# Peripheral.net
KiCad netlist of a schematic drawn in Altium Designer
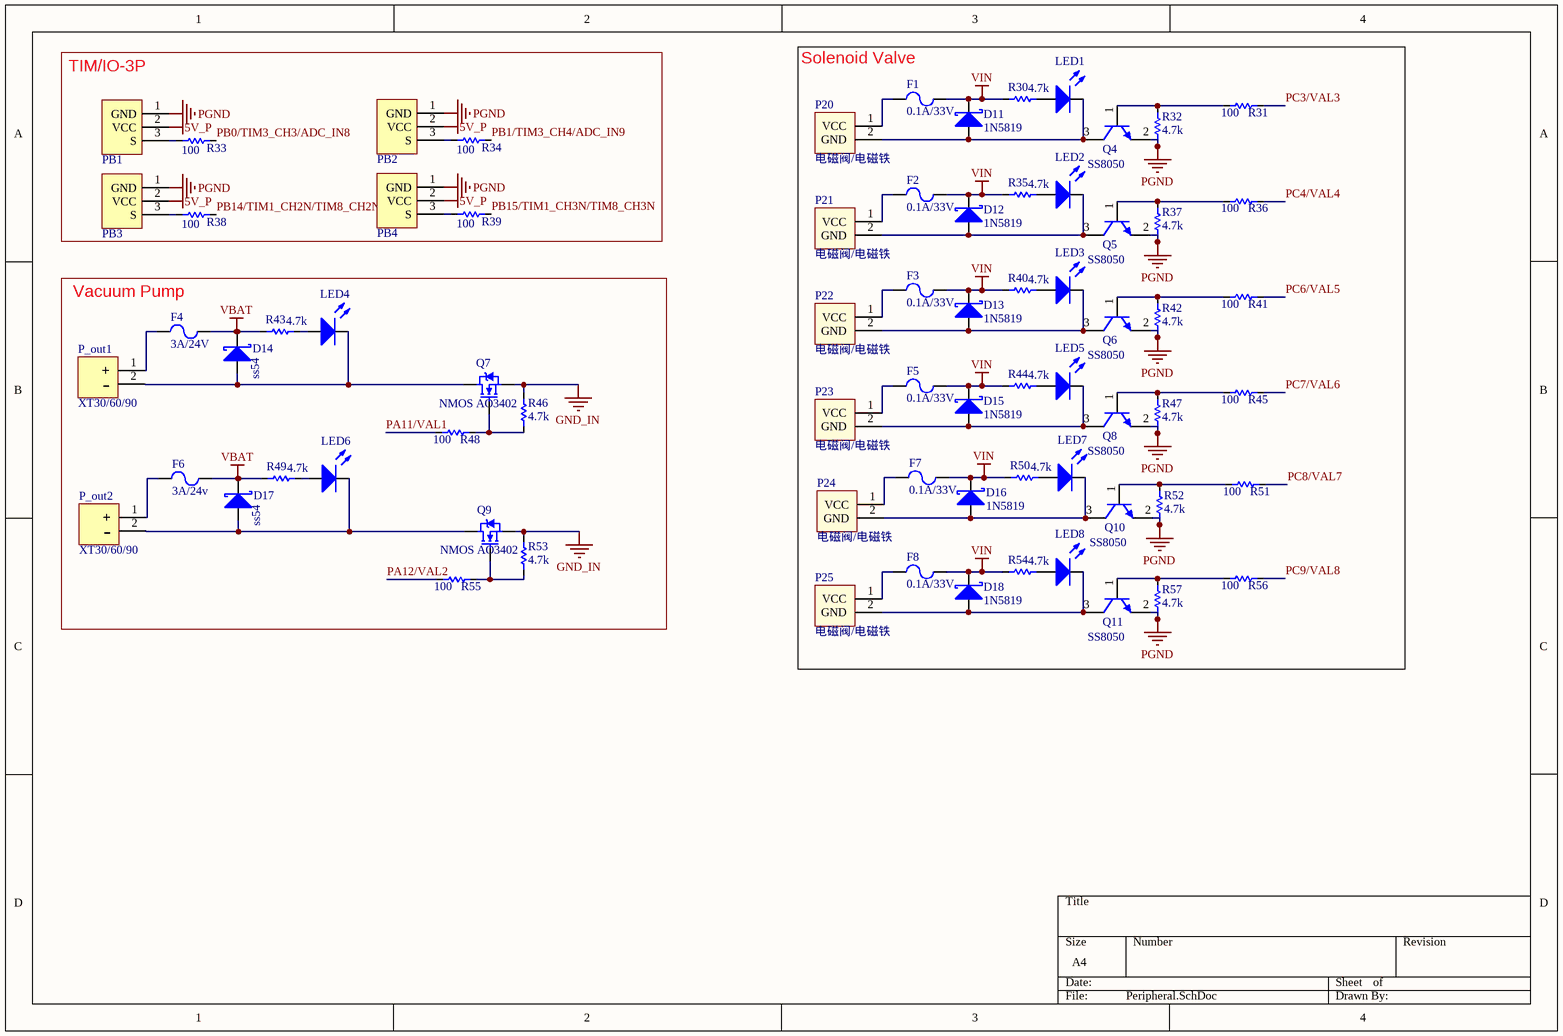
[diagram p0: Peripheral.SchDoc]

(export (version "E")
  (design (tool "Eeschema 10.0.6"))
  (components
    (comp (ref "D11")
      (value "1N5819")
      (footprint "SOD-323-")
      (description "Schottky Diode")
      (fields (field (name "PUBLISHER") "Altium Limited"))
      (libsource (lib "MyComponents_v2.5") (part "D Schottky"))
    )
    (comp (ref "D12")
      (value "1N5819")
      (footprint "SOD-323-")
      (description "Schottky Diode")
      (fields (field (name "PUBLISHER") "Altium Limited"))
      (libsource (lib "MyComponents_v2.5") (part "D Schottky"))
    )
    (comp (ref "D13")
      (value "1N5819")
      (footprint "SOD-323-")
      (description "Schottky Diode")
      (fields (field (name "PUBLISHER") "Altium Limited"))
      (libsource (lib "MyComponents_v2.5") (part "D Schottky"))
    )
    (comp (ref "D14")
      (value "ss54")
      (footprint "SMAF/DO-214AC")
      (description "Schottky Diode")
      (fields (field (name "PUBLISHER") "Altium Limited"))
      (libsource (lib "MyComponents_v2.5") (part "D Schottky_SOD323"))
    )
    (comp (ref "D15")
      (value "1N5819")
      (footprint "SOD-323-")
      (description "Schottky Diode")
      (fields (field (name "PUBLISHER") "Altium Limited"))
      (libsource (lib "MyComponents_v2.5") (part "D Schottky"))
    )
    (comp (ref "D16")
      (value "1N5819")
      (footprint "SOD-323-")
      (description "Schottky Diode")
      (fields (field (name "PUBLISHER") "Altium Limited"))
      (libsource (lib "MyComponents_v2.5") (part "D Schottky"))
    )
    (comp (ref "D17")
      (value "ss54")
      (footprint "SMAF/DO-214AC")
      (description "Schottky Diode")
      (fields (field (name "PUBLISHER") "Altium Limited"))
      (libsource (lib "MyComponents_v2.5") (part "D Schottky_SOD323"))
    )
    (comp (ref "D18")
      (value "1N5819")
      (footprint "SOD-323-")
      (description "Schottky Diode")
      (fields (field (name "PUBLISHER") "Altium Limited"))
      (libsource (lib "MyComponents_v2.5") (part "D Schottky"))
    )
    (comp (ref "F1")
      (value "0.1A/33V")
      (footprint "0603C")
      (description "0603自恢复保险丝")
      (libsource (lib "MyComponents_v2.5") (part "Finance"))
    )
    (comp (ref "F2")
      (value "0.1A/33V")
      (footprint "0603C")
      (description "0603自恢复保险丝")
      (libsource (lib "MyComponents_v2.5") (part "Finance"))
    )
    (comp (ref "F3")
      (value "0.1A/33V")
      (footprint "0603C")
      (description "0603自恢复保险丝")
      (libsource (lib "MyComponents_v2.5") (part "Finance"))
    )
    (comp (ref "F4")
      (value "3A/24V")
      (footprint "0603C")
      (description "0603自恢复保险丝")
      (libsource (lib "MyComponents_v2.5") (part "Finance"))
    )
    (comp (ref "F5")
      (value "0.1A/33V")
      (footprint "0603C")
      (description "0603自恢复保险丝")
      (libsource (lib "MyComponents_v2.5") (part "Finance"))
    )
    (comp (ref "F6")
      (value "3A/24v")
      (footprint "0603C")
      (description "0603自恢复保险丝")
      (libsource (lib "MyComponents_v2.5") (part "Finance"))
    )
    (comp (ref "F7")
      (value "0.1A/33V")
      (footprint "0603C")
      (description "0603自恢复保险丝")
      (libsource (lib "MyComponents_v2.5") (part "Finance"))
    )
    (comp (ref "F8")
      (value "0.1A/33V")
      (footprint "0603C")
      (description "0603自恢复保险丝")
      (libsource (lib "MyComponents_v2.5") (part "Finance"))
    )
    (comp (ref "LED1")
      (value "LED_RED")
      (footprint "0603LED_B")
      (description "Typical RED, GREEN, YELLOW, AMBER GaAs LED")
      (fields (field (name "PUBLISHER") "Altium Limited"))
      (libsource (lib "MyComponents_v2.5") (part "LED"))
    )
    (comp (ref "LED2")
      (value "LED_RED")
      (footprint "0603LED_B")
      (description "Typical RED, GREEN, YELLOW, AMBER GaAs LED")
      (fields (field (name "PUBLISHER") "Altium Limited"))
      (libsource (lib "MyComponents_v2.5") (part "LED"))
    )
    (comp (ref "LED3")
      (value "LED_RED")
      (footprint "0603LED_B")
      (description "Typical RED, GREEN, YELLOW, AMBER GaAs LED")
      (fields (field (name "PUBLISHER") "Altium Limited"))
      (libsource (lib "MyComponents_v2.5") (part "LED"))
    )
    (comp (ref "LED4")
      (value "LED_RED")
      (footprint "0603LED_B")
      (description "Typical RED, GREEN, YELLOW, AMBER GaAs LED")
      (fields (field (name "PUBLISHER") "Altium Limited"))
      (libsource (lib "MyComponents_v2.5") (part "LED"))
    )
    (comp (ref "LED5")
      (value "LED_RED")
      (footprint "0603LED_B")
      (description "Typical RED, GREEN, YELLOW, AMBER GaAs LED")
      (fields (field (name "PUBLISHER") "Altium Limited"))
      (libsource (lib "MyComponents_v2.5") (part "LED"))
    )
    (comp (ref "LED6")
      (value "LED_RED")
      (footprint "0603LED_B")
      (description "Typical RED, GREEN, YELLOW, AMBER GaAs LED")
      (fields (field (name "PUBLISHER") "Altium Limited"))
      (libsource (lib "MyComponents_v2.5") (part "LED"))
    )
    (comp (ref "LED7")
      (value "LED_RED")
      (footprint "0603LED_B")
      (description "Typical RED, GREEN, YELLOW, AMBER GaAs LED")
      (fields (field (name "PUBLISHER") "Altium Limited"))
      (libsource (lib "MyComponents_v2.5") (part "LED"))
    )
    (comp (ref "LED8")
      (value "LED_RED")
      (footprint "0603LED_B")
      (description "Typical RED, GREEN, YELLOW, AMBER GaAs LED")
      (fields (field (name "PUBLISHER") "Altium Limited"))
      (libsource (lib "MyComponents_v2.5") (part "LED"))
    )
    (comp (ref "P20")
      (value "电磁阀/电磁铁")
      (footprint "HY2.00MM 2X1_立式")
      (libsource (lib "MyComponents_v2.5") (part "电磁阀/电磁铁"))
    )
    (comp (ref "P21")
      (value "电磁阀/电磁铁")
      (footprint "HY2.00MM 2X1_立式")
      (libsource (lib "MyComponents_v2.5") (part "电磁阀/电磁铁"))
    )
    (comp (ref "P22")
      (value "电磁阀/电磁铁")
      (footprint "HY2.00MM 2X1_立式")
      (libsource (lib "MyComponents_v2.5") (part "电磁阀/电磁铁"))
    )
    (comp (ref "P23")
      (value "电磁阀/电磁铁")
      (footprint "HY2.00MM 2X1_立式")
      (libsource (lib "MyComponents_v2.5") (part "电磁阀/电磁铁"))
    )
    (comp (ref "P24")
      (value "电磁阀/电磁铁")
      (footprint "HY2.00MM 2X1_立式")
      (libsource (lib "MyComponents_v2.5") (part "电磁阀/电磁铁"))
    )
    (comp (ref "P25")
      (value "电磁阀/电磁铁")
      (footprint "HY2.00MM 2X1_立式")
      (libsource (lib "MyComponents_v2.5") (part "电磁阀/电磁铁"))
    )
    (comp (ref "PB1")
      (value "3Pin_IO")
      (footprint "HY2.00MM 3x1立式")
      (description "3pin input/output. V+S+G")
      (libsource (lib "MyComponents_v2.5") (part "3Pin_IO"))
    )
    (comp (ref "PB2")
      (value "3Pin_IO")
      (footprint "HY2.00MM 3x1立式")
      (description "3pin input/output. V+S+G")
      (libsource (lib "MyComponents_v2.5") (part "3Pin_IO"))
    )
    (comp (ref "PB3")
      (value "3Pin_IO")
      (footprint "HY2.00MM 3x1立式")
      (description "3pin input/output. V+S+G")
      (libsource (lib "MyComponents_v2.5") (part "3Pin_IO"))
    )
    (comp (ref "PB4")
      (value "3Pin_IO")
      (footprint "HY2.00MM 3x1立式")
      (description "3pin input/output. V+S+G")
      (libsource (lib "MyComponents_v2.5") (part "3Pin_IO"))
    )
    (comp (ref "P_out1")
      (value "XT30/60/90")
      (footprint "XT30UPB-FEMALE")
      (libsource (lib "MyComponents_v2.5") (part "XT30/60/90"))
    )
    (comp (ref "P_out2")
      (value "XT30/60/90")
      (footprint "XT30UPB-FEMALE")
      (libsource (lib "MyComponents_v2.5") (part "XT30/60/90"))
    )
    (comp (ref "Q4")
      (value "SS8050")
      (footprint "SOT-23-3")
      (description "NPN Bipolar Transistor")
      (fields (field (name "PUBLISHER") "Altium Limited"))
      (libsource (lib "MyComponents_v2.5") (part "NPN"))
    )
    (comp (ref "Q5")
      (value "SS8050")
      (footprint "SOT-23-3")
      (description "NPN Bipolar Transistor")
      (fields (field (name "PUBLISHER") "Altium Limited"))
      (libsource (lib "MyComponents_v2.5") (part "NPN"))
    )
    (comp (ref "Q6")
      (value "SS8050")
      (footprint "SOT-23-3")
      (description "NPN Bipolar Transistor")
      (fields (field (name "PUBLISHER") "Altium Limited"))
      (libsource (lib "MyComponents_v2.5") (part "NPN"))
    )
    (comp (ref "Q7")
      (value "NMOS AO3402")
      (footprint "SOT-23-3")
      (description "N-Channel Power MOSFET")
      (fields (field (name "PUBLISHER") "Altium Limited"))
      (libsource (lib "MyComponents_v2.5") (part "NMOS(SOT23)"))
    )
    (comp (ref "Q8")
      (value "SS8050")
      (footprint "SOT-23-3")
      (description "NPN Bipolar Transistor")
      (fields (field (name "PUBLISHER") "Altium Limited"))
      (libsource (lib "MyComponents_v2.5") (part "NPN"))
    )
    (comp (ref "Q9")
      (value "NMOS AO3402")
      (footprint "SOT-23-3")
      (description "N-Channel Power MOSFET")
      (fields (field (name "PUBLISHER") "Altium Limited"))
      (libsource (lib "MyComponents_v2.5") (part "NMOS(SOT23)"))
    )
    (comp (ref "Q10")
      (value "SS8050")
      (footprint "SOT-23-3")
      (description "NPN Bipolar Transistor")
      (fields (field (name "PUBLISHER") "Altium Limited"))
      (libsource (lib "MyComponents_v2.5") (part "NPN"))
    )
    (comp (ref "Q11")
      (value "SS8050")
      (footprint "SOT-23-3")
      (description "NPN Bipolar Transistor")
      (fields (field (name "PUBLISHER") "Altium Limited"))
      (libsource (lib "MyComponents_v2.5") (part "NPN"))
    )
    (comp (ref "R30")
      (value "4.7k")
      (footprint "0603R")
      (description "Resistor")
      (fields (field (name "PUBLISHER") "Altium Limited"))
      (libsource (lib "MyComponents_v2.5") (part "Res1"))
    )
    (comp (ref "R31")
      (value "100")
      (footprint "0603R")
      (description "Resistor")
      (fields (field (name "PUBLISHER") "Altium Limited"))
      (libsource (lib "MyComponents_v2.5") (part "Res1"))
    )
    (comp (ref "R32")
      (value "4.7k")
      (footprint "0603R")
      (description "Resistor")
      (fields (field (name "PUBLISHER") "Altium Limited"))
      (libsource (lib "MyComponents_v2.4") (part "Res1"))
    )
    (comp (ref "R33")
      (value "100")
      (footprint "0603R")
      (description "Resistor")
      (fields (field (name "PUBLISHER") "Altium Limited"))
      (libsource (lib "MyComponents_v2.5") (part "Res1"))
    )
    (comp (ref "R34")
      (value "100")
      (footprint "0603R")
      (description "Resistor")
      (fields (field (name "PUBLISHER") "Altium Limited"))
      (libsource (lib "MyComponents_v2.5") (part "Res1"))
    )
    (comp (ref "R35")
      (value "4.7k")
      (footprint "0603R")
      (description "Resistor")
      (fields (field (name "PUBLISHER") "Altium Limited"))
      (libsource (lib "MyComponents_v2.5") (part "Res1"))
    )
    (comp (ref "R36")
      (value "100")
      (footprint "0603R")
      (description "Resistor")
      (fields (field (name "PUBLISHER") "Altium Limited"))
      (libsource (lib "MyComponents_v2.5") (part "Res1"))
    )
    (comp (ref "R37")
      (value "4.7k")
      (footprint "0603R")
      (description "Resistor")
      (fields (field (name "PUBLISHER") "Altium Limited"))
      (libsource (lib "MyComponents_v2.4") (part "Res1"))
    )
    (comp (ref "R38")
      (value "100")
      (footprint "0603R")
      (description "Resistor")
      (fields (field (name "PUBLISHER") "Altium Limited"))
      (libsource (lib "MyComponents_v2.5") (part "Res1"))
    )
    (comp (ref "R39")
      (value "100")
      (footprint "0603R")
      (description "Resistor")
      (fields (field (name "PUBLISHER") "Altium Limited"))
      (libsource (lib "MyComponents_v2.5") (part "Res1"))
    )
    (comp (ref "R40")
      (value "4.7k")
      (footprint "0603R")
      (description "Resistor")
      (fields (field (name "PUBLISHER") "Altium Limited"))
      (libsource (lib "MyComponents_v2.5") (part "Res1"))
    )
    (comp (ref "R41")
      (value "100")
      (footprint "0603R")
      (description "Resistor")
      (fields (field (name "PUBLISHER") "Altium Limited"))
      (libsource (lib "MyComponents_v2.5") (part "Res1"))
    )
    (comp (ref "R42")
      (value "4.7k")
      (footprint "0603R")
      (description "Resistor")
      (fields (field (name "PUBLISHER") "Altium Limited"))
      (libsource (lib "MyComponents_v2.4") (part "Res1"))
    )
    (comp (ref "R43")
      (value "4.7k")
      (footprint "0603R")
      (description "Resistor")
      (fields (field (name "PUBLISHER") "Altium Limited"))
      (libsource (lib "MyComponents_v2.5") (part "Res1"))
    )
    (comp (ref "R44")
      (value "4.7k")
      (footprint "0603R")
      (description "Resistor")
      (fields (field (name "PUBLISHER") "Altium Limited"))
      (libsource (lib "MyComponents_v2.5") (part "Res1"))
    )
    (comp (ref "R45")
      (value "100")
      (footprint "0603R")
      (description "Resistor")
      (fields (field (name "PUBLISHER") "Altium Limited"))
      (libsource (lib "MyComponents_v2.5") (part "Res1"))
    )
    (comp (ref "R46")
      (value "4.7k")
      (footprint "0603R")
      (description "Resistor")
      (fields (field (name "PUBLISHER") "Altium Limited"))
      (libsource (lib "MyComponents_v2.4") (part "Res1"))
    )
    (comp (ref "R47")
      (value "4.7k")
      (footprint "0603R")
      (description "Resistor")
      (fields (field (name "PUBLISHER") "Altium Limited"))
      (libsource (lib "MyComponents_v2.4") (part "Res1"))
    )
    (comp (ref "R48")
      (value "100")
      (footprint "0603R")
      (description "Resistor")
      (fields (field (name "PUBLISHER") "Altium Limited"))
      (libsource (lib "MyComponents_v2.5") (part "Res1"))
    )
    (comp (ref "R49")
      (value "4.7k")
      (footprint "0603R")
      (description "Resistor")
      (fields (field (name "PUBLISHER") "Altium Limited"))
      (libsource (lib "MyComponents_v2.5") (part "Res1"))
    )
    (comp (ref "R50")
      (value "4.7k")
      (footprint "0603R")
      (description "Resistor")
      (fields (field (name "PUBLISHER") "Altium Limited"))
      (libsource (lib "MyComponents_v2.5") (part "Res1"))
    )
    (comp (ref "R51")
      (value "100")
      (footprint "0603R")
      (description "Resistor")
      (fields (field (name "PUBLISHER") "Altium Limited"))
      (libsource (lib "MyComponents_v2.5") (part "Res1"))
    )
    (comp (ref "R52")
      (value "4.7k")
      (footprint "0603R")
      (description "Resistor")
      (fields (field (name "PUBLISHER") "Altium Limited"))
      (libsource (lib "MyComponents_v2.4") (part "Res1"))
    )
    (comp (ref "R53")
      (value "4.7k")
      (footprint "0603R")
      (description "Resistor")
      (fields (field (name "PUBLISHER") "Altium Limited"))
      (libsource (lib "MyComponents_v2.4") (part "Res1"))
    )
    (comp (ref "R54")
      (value "4.7k")
      (footprint "0603R")
      (description "Resistor")
      (fields (field (name "PUBLISHER") "Altium Limited"))
      (libsource (lib "MyComponents_v2.5") (part "Res1"))
    )
    (comp (ref "R55")
      (value "100")
      (footprint "0603R")
      (description "Resistor")
      (fields (field (name "PUBLISHER") "Altium Limited"))
      (libsource (lib "MyComponents_v2.5") (part "Res1"))
    )
    (comp (ref "R56")
      (value "100")
      (footprint "0603R")
      (description "Resistor")
      (fields (field (name "PUBLISHER") "Altium Limited"))
      (libsource (lib "MyComponents_v2.5") (part "Res1"))
    )
    (comp (ref "R57")
      (value "4.7k")
      (footprint "0603R")
      (description "Resistor")
      (fields (field (name "PUBLISHER") "Altium Limited"))
      (libsource (lib "MyComponents_v2.4") (part "Res1"))
    )
  )
  (nets
    (net (code "1") (name "/PA11{slash}VAL1") (class "Default")
      (node (ref "R48") (pin "1") (pinfunction "1_1") (pintype "passive"))
    )
    (net (code "2") (name "/PA12{slash}VAL2") (class "Default")
      (node (ref "R55") (pin "1") (pinfunction "1_1") (pintype "passive"))
    )
    (net (code "3") (name "/PB0{slash}TIM3_CH3{slash}ADC_IN8") (class "Default")
      (node (ref "R33") (pin "2") (pinfunction "2_2") (pintype "passive"))
    )
    (net (code "4") (name "/PB1{slash}TIM3_CH4{slash}ADC_IN9") (class "Default")
      (node (ref "R34") (pin "2") (pinfunction "2_2") (pintype "passive"))
    )
    (net (code "5") (name "/PB14{slash}TIM1_CH2N{slash}TIM8_CH2N") (class "Default")
      (node (ref "R38") (pin "2") (pinfunction "2_2") (pintype "passive"))
    )
    (net (code "6") (name "/PB15{slash}TIM1_CH3N{slash}TIM8_CH3N") (class "Default")
      (node (ref "R39") (pin "2") (pinfunction "2_2") (pintype "passive"))
    )
    (net (code "7") (name "/PC3{slash}VAL3") (class "Default")
      (node (ref "R31") (pin "2") (pinfunction "2_2") (pintype "passive"))
    )
    (net (code "8") (name "/PC4{slash}VAL4") (class "Default")
      (node (ref "R36") (pin "2") (pinfunction "2_2") (pintype "passive"))
    )
    (net (code "9") (name "/PC6{slash}VAL5") (class "Default")
      (node (ref "R41") (pin "2") (pinfunction "2_2") (pintype "passive"))
    )
    (net (code "10") (name "/PC7{slash}VAL6") (class "Default")
      (node (ref "R45") (pin "2") (pinfunction "2_2") (pintype "passive"))
    )
    (net (code "11") (name "/PC8{slash}VAL7") (class "Default")
      (node (ref "R51") (pin "2") (pinfunction "2_2") (pintype "passive"))
    )
    (net (code "12") (name "/PC9{slash}VAL8") (class "Default")
      (node (ref "R56") (pin "2") (pinfunction "2_2") (pintype "passive"))
    )
    (net (code "13") (name "5V_P") (class "Default")
      (node (ref "PB1") (pin "2") (pinfunction "VCC_2") (pintype "passive"))
      (node (ref "PB2") (pin "2") (pinfunction "VCC_2") (pintype "passive"))
      (node (ref "PB3") (pin "2") (pinfunction "VCC_2") (pintype "passive"))
      (node (ref "PB4") (pin "2") (pinfunction "VCC_2") (pintype "passive"))
    )
    (net (code "14") (name "GND_IN") (class "Default")
      (node (ref "Q7") (pin "2") (pinfunction "S_2") (pintype "passive"))
      (node (ref "Q9") (pin "2") (pinfunction "S_2") (pintype "passive"))
      (node (ref "R46") (pin "2") (pinfunction "2_2") (pintype "passive"))
      (node (ref "R53") (pin "2") (pinfunction "2_2") (pintype "passive"))
    )
    (net (code "15") (name "Net-(LED1-Pad1)") (class "Default")
      (node (ref "LED1") (pin "1") (pinfunction "1_1") (pintype "passive"))
      (node (ref "R30") (pin "2") (pinfunction "2_2") (pintype "passive"))
    )
    (net (code "16") (name "Net-(LED2-Pad1)") (class "Default")
      (node (ref "LED2") (pin "1") (pinfunction "1_1") (pintype "passive"))
      (node (ref "R35") (pin "2") (pinfunction "2_2") (pintype "passive"))
    )
    (net (code "17") (name "Net-(LED3-Pad1)") (class "Default")
      (node (ref "LED3") (pin "1") (pinfunction "1_1") (pintype "passive"))
      (node (ref "R40") (pin "2") (pinfunction "2_2") (pintype "passive"))
    )
    (net (code "18") (name "Net-(LED4-Pad1)") (class "Default")
      (node (ref "LED4") (pin "1") (pinfunction "1_1") (pintype "passive"))
      (node (ref "R43") (pin "2") (pinfunction "2_2") (pintype "passive"))
    )
    (net (code "19") (name "Net-(LED5-Pad1)") (class "Default")
      (node (ref "LED5") (pin "1") (pinfunction "1_1") (pintype "passive"))
      (node (ref "R44") (pin "2") (pinfunction "2_2") (pintype "passive"))
    )
    (net (code "20") (name "Net-(LED6-Pad1)") (class "Default")
      (node (ref "LED6") (pin "1") (pinfunction "1_1") (pintype "passive"))
      (node (ref "R49") (pin "2") (pinfunction "2_2") (pintype "passive"))
    )
    (net (code "21") (name "Net-(LED7-Pad1)") (class "Default")
      (node (ref "LED7") (pin "1") (pinfunction "1_1") (pintype "passive"))
      (node (ref "R50") (pin "2") (pinfunction "2_2") (pintype "passive"))
    )
    (net (code "22") (name "Net-(LED8-Pad1)") (class "Default")
      (node (ref "LED8") (pin "1") (pinfunction "1_1") (pintype "passive"))
      (node (ref "R54") (pin "2") (pinfunction "2_2") (pintype "passive"))
    )
    (net (code "23") (name "Net-(P20-GND)") (class "Default")
      (node (ref "D11") (pin "1") (pinfunction "1_1") (pintype "passive"))
      (node (ref "LED1") (pin "2") (pinfunction "2_2") (pintype "passive"))
      (node (ref "P20") (pin "2") (pinfunction "GND_2") (pintype "passive"))
      (node (ref "Q4") (pin "3") (pinfunction "C_3") (pintype "passive"))
    )
    (net (code "24") (name "Net-(P20-VCC)") (class "Default")
      (node (ref "F1") (pin "1") (pinfunction "1_1") (pintype "passive"))
      (node (ref "P20") (pin "1") (pinfunction "VCC_1") (pintype "passive"))
    )
    (net (code "25") (name "Net-(P21-GND)") (class "Default")
      (node (ref "D12") (pin "1") (pinfunction "1_1") (pintype "passive"))
      (node (ref "LED2") (pin "2") (pinfunction "2_2") (pintype "passive"))
      (node (ref "P21") (pin "2") (pinfunction "GND_2") (pintype "passive"))
      (node (ref "Q5") (pin "3") (pinfunction "C_3") (pintype "passive"))
    )
    (net (code "26") (name "Net-(P21-VCC)") (class "Default")
      (node (ref "F2") (pin "1") (pinfunction "1_1") (pintype "passive"))
      (node (ref "P21") (pin "1") (pinfunction "VCC_1") (pintype "passive"))
    )
    (net (code "27") (name "Net-(P22-GND)") (class "Default")
      (node (ref "D13") (pin "1") (pinfunction "1_1") (pintype "passive"))
      (node (ref "LED3") (pin "2") (pinfunction "2_2") (pintype "passive"))
      (node (ref "P22") (pin "2") (pinfunction "GND_2") (pintype "passive"))
      (node (ref "Q6") (pin "3") (pinfunction "C_3") (pintype "passive"))
    )
    (net (code "28") (name "Net-(P22-VCC)") (class "Default")
      (node (ref "F3") (pin "1") (pinfunction "1_1") (pintype "passive"))
      (node (ref "P22") (pin "1") (pinfunction "VCC_1") (pintype "passive"))
    )
    (net (code "29") (name "Net-(P23-GND)") (class "Default")
      (node (ref "D15") (pin "1") (pinfunction "1_1") (pintype "passive"))
      (node (ref "LED5") (pin "2") (pinfunction "2_2") (pintype "passive"))
      (node (ref "P23") (pin "2") (pinfunction "GND_2") (pintype "passive"))
      (node (ref "Q8") (pin "3") (pinfunction "C_3") (pintype "passive"))
    )
    (net (code "30") (name "Net-(P23-VCC)") (class "Default")
      (node (ref "F5") (pin "1") (pinfunction "1_1") (pintype "passive"))
      (node (ref "P23") (pin "1") (pinfunction "VCC_1") (pintype "passive"))
    )
    (net (code "31") (name "Net-(P24-GND)") (class "Default")
      (node (ref "D16") (pin "1") (pinfunction "1_1") (pintype "passive"))
      (node (ref "LED7") (pin "2") (pinfunction "2_2") (pintype "passive"))
      (node (ref "P24") (pin "2") (pinfunction "GND_2") (pintype "passive"))
      (node (ref "Q10") (pin "3") (pinfunction "C_3") (pintype "passive"))
    )
    (net (code "32") (name "Net-(P24-VCC)") (class "Default")
      (node (ref "F7") (pin "1") (pinfunction "1_1") (pintype "passive"))
      (node (ref "P24") (pin "1") (pinfunction "VCC_1") (pintype "passive"))
    )
    (net (code "33") (name "Net-(P25-GND)") (class "Default")
      (node (ref "D18") (pin "1") (pinfunction "1_1") (pintype "passive"))
      (node (ref "LED8") (pin "2") (pinfunction "2_2") (pintype "passive"))
      (node (ref "P25") (pin "2") (pinfunction "GND_2") (pintype "passive"))
      (node (ref "Q11") (pin "3") (pinfunction "C_3") (pintype "passive"))
    )
    (net (code "34") (name "Net-(P25-VCC)") (class "Default")
      (node (ref "F8") (pin "1") (pinfunction "1_1") (pintype "passive"))
      (node (ref "P25") (pin "1") (pinfunction "VCC_1") (pintype "passive"))
    )
    (net (code "35") (name "Net-(PB1-S)") (class "Default")
      (node (ref "PB1") (pin "3") (pinfunction "S_3") (pintype "passive"))
      (node (ref "R33") (pin "1") (pinfunction "1_1") (pintype "passive"))
    )
    (net (code "36") (name "Net-(PB2-S)") (class "Default")
      (node (ref "PB2") (pin "3") (pinfunction "S_3") (pintype "passive"))
      (node (ref "R34") (pin "1") (pinfunction "1_1") (pintype "passive"))
    )
    (net (code "37") (name "Net-(PB3-S)") (class "Default")
      (node (ref "PB3") (pin "3") (pinfunction "S_3") (pintype "passive"))
      (node (ref "R38") (pin "1") (pinfunction "1_1") (pintype "passive"))
    )
    (net (code "38") (name "Net-(PB4-S)") (class "Default")
      (node (ref "PB4") (pin "3") (pinfunction "S_3") (pintype "passive"))
      (node (ref "R39") (pin "1") (pinfunction "1_1") (pintype "passive"))
    )
    (net (code "39") (name "Net-(P_out1-+)") (class "Default")
      (node (ref "F4") (pin "1") (pinfunction "1_1") (pintype "passive"))
      (node (ref "P_out1") (pin "1") (pinfunction "+_1") (pintype "passive"))
    )
    (net (code "40") (name "Net-(P_out1--)") (class "Default")
      (node (ref "D14") (pin "1") (pinfunction "1_1") (pintype "passive"))
      (node (ref "LED4") (pin "2") (pinfunction "2_2") (pintype "passive"))
      (node (ref "P_out1") (pin "2") (pinfunction "-_2") (pintype "passive"))
      (node (ref "Q7") (pin "3") (pinfunction "D_3") (pintype "passive"))
    )
    (net (code "41") (name "Net-(P_out2-+)") (class "Default")
      (node (ref "F6") (pin "1") (pinfunction "1_1") (pintype "passive"))
      (node (ref "P_out2") (pin "1") (pinfunction "+_1") (pintype "passive"))
    )
    (net (code "42") (name "Net-(P_out2--)") (class "Default")
      (node (ref "D17") (pin "1") (pinfunction "1_1") (pintype "passive"))
      (node (ref "LED6") (pin "2") (pinfunction "2_2") (pintype "passive"))
      (node (ref "P_out2") (pin "2") (pinfunction "-_2") (pintype "passive"))
      (node (ref "Q9") (pin "3") (pinfunction "D_3") (pintype "passive"))
    )
    (net (code "43") (name "Net-(Q4-B)") (class "Default")
      (node (ref "Q4") (pin "1") (pinfunction "B_1") (pintype "passive"))
      (node (ref "R31") (pin "1") (pinfunction "1_1") (pintype "passive"))
      (node (ref "R32") (pin "2") (pinfunction "2_2") (pintype "passive"))
    )
    (net (code "44") (name "Net-(Q5-B)") (class "Default")
      (node (ref "Q5") (pin "1") (pinfunction "B_1") (pintype "passive"))
      (node (ref "R36") (pin "1") (pinfunction "1_1") (pintype "passive"))
      (node (ref "R37") (pin "2") (pinfunction "2_2") (pintype "passive"))
    )
    (net (code "45") (name "Net-(Q6-B)") (class "Default")
      (node (ref "Q6") (pin "1") (pinfunction "B_1") (pintype "passive"))
      (node (ref "R41") (pin "1") (pinfunction "1_1") (pintype "passive"))
      (node (ref "R42") (pin "2") (pinfunction "2_2") (pintype "passive"))
    )
    (net (code "46") (name "Net-(Q7-G)") (class "Default")
      (node (ref "Q7") (pin "1") (pinfunction "G_1") (pintype "passive"))
      (node (ref "R46") (pin "1") (pinfunction "1_1") (pintype "passive"))
      (node (ref "R48") (pin "2") (pinfunction "2_2") (pintype "passive"))
    )
    (net (code "47") (name "Net-(Q8-B)") (class "Default")
      (node (ref "Q8") (pin "1") (pinfunction "B_1") (pintype "passive"))
      (node (ref "R45") (pin "1") (pinfunction "1_1") (pintype "passive"))
      (node (ref "R47") (pin "2") (pinfunction "2_2") (pintype "passive"))
    )
    (net (code "48") (name "Net-(Q9-G)") (class "Default")
      (node (ref "Q9") (pin "1") (pinfunction "G_1") (pintype "passive"))
      (node (ref "R53") (pin "1") (pinfunction "1_1") (pintype "passive"))
      (node (ref "R55") (pin "2") (pinfunction "2_2") (pintype "passive"))
    )
    (net (code "49") (name "Net-(Q10-B)") (class "Default")
      (node (ref "Q10") (pin "1") (pinfunction "B_1") (pintype "passive"))
      (node (ref "R51") (pin "1") (pinfunction "1_1") (pintype "passive"))
      (node (ref "R52") (pin "2") (pinfunction "2_2") (pintype "passive"))
    )
    (net (code "50") (name "Net-(Q11-B)") (class "Default")
      (node (ref "Q11") (pin "1") (pinfunction "B_1") (pintype "passive"))
      (node (ref "R56") (pin "1") (pinfunction "1_1") (pintype "passive"))
      (node (ref "R57") (pin "2") (pinfunction "2_2") (pintype "passive"))
    )
    (net (code "51") (name "PGND") (class "Default")
      (node (ref "PB1") (pin "1") (pinfunction "GND_1") (pintype "passive"))
      (node (ref "PB2") (pin "1") (pinfunction "GND_1") (pintype "passive"))
      (node (ref "PB3") (pin "1") (pinfunction "GND_1") (pintype "passive"))
      (node (ref "PB4") (pin "1") (pinfunction "GND_1") (pintype "passive"))
      (node (ref "Q10") (pin "2") (pinfunction "E_2") (pintype "passive"))
      (node (ref "Q11") (pin "2") (pinfunction "E_2") (pintype "passive"))
      (node (ref "Q4") (pin "2") (pinfunction "E_2") (pintype "passive"))
      (node (ref "Q5") (pin "2") (pinfunction "E_2") (pintype "passive"))
      (node (ref "Q6") (pin "2") (pinfunction "E_2") (pintype "passive"))
      (node (ref "Q8") (pin "2") (pinfunction "E_2") (pintype "passive"))
      (node (ref "R32") (pin "1") (pinfunction "1_1") (pintype "passive"))
      (node (ref "R37") (pin "1") (pinfunction "1_1") (pintype "passive"))
      (node (ref "R42") (pin "1") (pinfunction "1_1") (pintype "passive"))
      (node (ref "R47") (pin "1") (pinfunction "1_1") (pintype "passive"))
      (node (ref "R52") (pin "1") (pinfunction "1_1") (pintype "passive"))
      (node (ref "R57") (pin "1") (pinfunction "1_1") (pintype "passive"))
    )
    (net (code "52") (name "VBAT") (class "Default")
      (node (ref "D14") (pin "2") (pinfunction "2_2") (pintype "passive"))
      (node (ref "D17") (pin "2") (pinfunction "2_2") (pintype "passive"))
      (node (ref "F4") (pin "2") (pinfunction "2_2") (pintype "passive"))
      (node (ref "F6") (pin "2") (pinfunction "2_2") (pintype "passive"))
      (node (ref "R43") (pin "1") (pinfunction "1_1") (pintype "passive"))
      (node (ref "R49") (pin "1") (pinfunction "1_1") (pintype "passive"))
    )
    (net (code "53") (name "VIN") (class "Default")
      (node (ref "D11") (pin "2") (pinfunction "2_2") (pintype "passive"))
      (node (ref "D12") (pin "2") (pinfunction "2_2") (pintype "passive"))
      (node (ref "D13") (pin "2") (pinfunction "2_2") (pintype "passive"))
      (node (ref "D15") (pin "2") (pinfunction "2_2") (pintype "passive"))
      (node (ref "D16") (pin "2") (pinfunction "2_2") (pintype "passive"))
      (node (ref "D18") (pin "2") (pinfunction "2_2") (pintype "passive"))
      (node (ref "F1") (pin "2") (pinfunction "2_2") (pintype "passive"))
      (node (ref "F2") (pin "2") (pinfunction "2_2") (pintype "passive"))
      (node (ref "F3") (pin "2") (pinfunction "2_2") (pintype "passive"))
      (node (ref "F5") (pin "2") (pinfunction "2_2") (pintype "passive"))
      (node (ref "F7") (pin "2") (pinfunction "2_2") (pintype "passive"))
      (node (ref "F8") (pin "2") (pinfunction "2_2") (pintype "passive"))
      (node (ref "R30") (pin "1") (pinfunction "1_1") (pintype "passive"))
      (node (ref "R35") (pin "1") (pinfunction "1_1") (pintype "passive"))
      (node (ref "R40") (pin "1") (pinfunction "1_1") (pintype "passive"))
      (node (ref "R44") (pin "1") (pinfunction "1_1") (pintype "passive"))
      (node (ref "R50") (pin "1") (pinfunction "1_1") (pintype "passive"))
      (node (ref "R54") (pin "1") (pinfunction "1_1") (pintype "passive"))
    )
  )
)
